# MicroControlador.net
KiCad netlist of a schematic drawn in Altium Designer
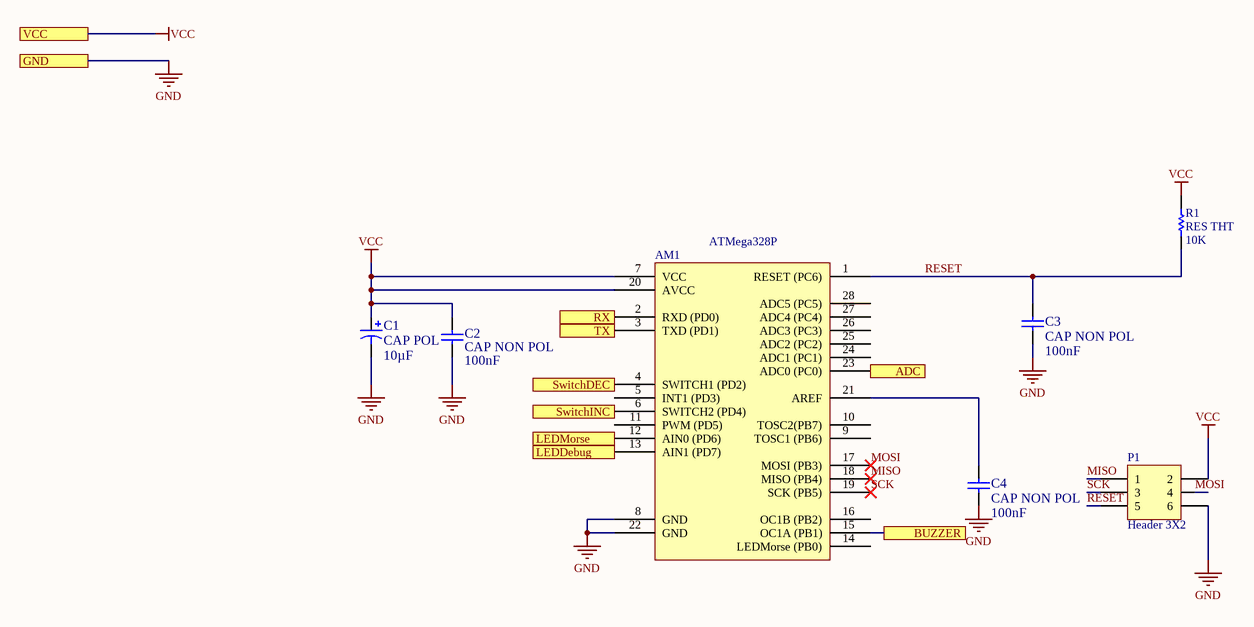
[diagram p0: MicroControlador.SchDoc]

(export (version "E")
  (design (tool "Eeschema 10.0.6"))
  (components
    (comp (ref "AM1")
      (value "ATMega328P")
      (footprint "ATMega328P")
      (libsource (lib "ATMega328P") (part "ATMega328P"))
    )
    (comp (ref "C1")
      (value "CAP POL")
      (footprint "CONDENS 10uF")
      (description "Polarized Capacitor (Axial)")
      (fields (field (name "ALTIUM_VALUE") "10µF") (field (name "PUBLISHER") "Altium Limited"))
      (libsource (lib "MySchem") (part "Cap Pol2"))
    )
    (comp (ref "C2")
      (value "CAP NON POL")
      (footprint "Capacitor 100nF")
      (description "Capacitor")
      (fields (field (name "ALTIUM_VALUE") "100nF") (field (name "PUBLISHER") "Altium Limited"))
      (libsource (lib "MySchem") (part "Cap"))
    )
    (comp (ref "C3")
      (value "CAP NON POL")
      (footprint "Capacitor 100nF")
      (description "Capacitor")
      (fields (field (name "ALTIUM_VALUE") "100nF") (field (name "PUBLISHER") "Altium Limited"))
      (libsource (lib "MySchem") (part "Cap"))
    )
    (comp (ref "C4")
      (value "CAP NON POL")
      (footprint "Capacitor 100nF")
      (description "Capacitor")
      (fields (field (name "ALTIUM_VALUE") "100nF") (field (name "PUBLISHER") "Altium Limited"))
      (libsource (lib "MySchem") (part "Cap"))
    )
    (comp (ref "P1")
      (value "Header 3X2")
      (footprint "Connector Header 3x2")
      (description "Header, 3-Pin, Dual row")
      (fields (field (name "PUBLISHER") "Altium Limited"))
      (libsource (lib "MySchematicConnector") (part "Header 3X2"))
    )
    (comp (ref "R1")
      (value "RES THT")
      (footprint "RESISTENCIA")
      (description "Resistor")
      (fields (field (name "ALTIUM_VALUE") "10K") (field (name "PUBLISHER") "Altium Limited"))
      (libsource (lib "MySchem") (part "Res1"))
    )
  )
  (nets
    (net (code "1") (name "/ADC") (class "Default")
      (node (ref "AM1") (pin "23") (pinfunction "ADC0_(PC0)_23") (pintype "passive"))
    )
    (net (code "2") (name "/BUZZER") (class "Default")
      (node (ref "AM1") (pin "15") (pinfunction "OC1A_(PB1)_15") (pintype "passive"))
    )
    (net (code "3") (name "/LEDDebug") (class "Default")
      (node (ref "AM1") (pin "13") (pinfunction "AIN1_(PD7)_13") (pintype "passive"))
    )
    (net (code "4") (name "/LEDMorse") (class "Default")
      (node (ref "AM1") (pin "12") (pinfunction "AIN0_(PD6)_12") (pintype "passive"))
    )
    (net (code "5") (name "/MISO") (class "Default")
      (node (ref "AM1") (pin "18") (pinfunction "MISO_(PB4)_18") (pintype "passive"))
      (node (ref "P1") (pin "1") (pinfunction "1_1") (pintype "passive"))
    )
    (net (code "6") (name "/MOSI") (class "Default")
      (node (ref "AM1") (pin "17") (pinfunction "MOSI_(PB3)_17") (pintype "passive"))
      (node (ref "P1") (pin "4") (pinfunction "4_4") (pintype "passive"))
    )
    (net (code "7") (name "/RESET") (class "Default")
      (node (ref "AM1") (pin "1") (pinfunction "RESET_(PC6)_1") (pintype "passive"))
      (node (ref "C3") (pin "2") (pinfunction "2_2") (pintype "passive"))
      (node (ref "P1") (pin "5") (pinfunction "5_5") (pintype "passive"))
      (node (ref "R1") (pin "1") (pinfunction "1_1") (pintype "passive"))
    )
    (net (code "8") (name "/RX") (class "Default")
      (node (ref "AM1") (pin "2") (pinfunction "RXD_(PD0)_2") (pintype "passive"))
    )
    (net (code "9") (name "/SCK") (class "Default")
      (node (ref "AM1") (pin "19") (pinfunction "SCK_(PB5)_19") (pintype "passive"))
      (node (ref "P1") (pin "3") (pinfunction "3_3") (pintype "passive"))
    )
    (net (code "10") (name "/SwitchDEC") (class "Default")
      (node (ref "AM1") (pin "4") (pinfunction "SWITCH1_(PD2)_4") (pintype "passive"))
    )
    (net (code "11") (name "/SwitchINC") (class "Default")
      (node (ref "AM1") (pin "6") (pinfunction "SWITCH2_(PD4)_6") (pintype "passive"))
    )
    (net (code "12") (name "/TX") (class "Default")
      (node (ref "AM1") (pin "3") (pinfunction "TXD_(PD1)_3") (pintype "passive"))
    )
    (net (code "13") (name "GND") (class "Default")
      (node (ref "AM1") (pin "22") (pinfunction "GND_22") (pintype "passive"))
      (node (ref "AM1") (pin "8") (pinfunction "GND_8") (pintype "passive"))
      (node (ref "C1") (pin "2") (pinfunction "2_2") (pintype "passive"))
      (node (ref "C2") (pin "2") (pinfunction "2_2") (pintype "passive"))
      (node (ref "C3") (pin "1") (pinfunction "1_1") (pintype "passive"))
      (node (ref "C4") (pin "1") (pinfunction "1_1") (pintype "passive"))
      (node (ref "P1") (pin "6") (pinfunction "6_6") (pintype "passive"))
    )
    (net (code "14") (name "Net-(AM1-AREF)") (class "Default")
      (node (ref "AM1") (pin "21") (pinfunction "AREF_21") (pintype "passive"))
      (node (ref "C4") (pin "2") (pinfunction "2_2") (pintype "passive"))
    )
    (net (code "15") (name "VCC") (class "Default")
      (node (ref "AM1") (pin "20") (pinfunction "AVCC_20") (pintype "passive"))
      (node (ref "AM1") (pin "7") (pinfunction "VCC_7") (pintype "passive"))
      (node (ref "C1") (pin "1") (pinfunction "1_1") (pintype "passive"))
      (node (ref "C2") (pin "1") (pinfunction "1_1") (pintype "passive"))
      (node (ref "P1") (pin "2") (pinfunction "2_2") (pintype "passive"))
      (node (ref "R1") (pin "2") (pinfunction "2_2") (pintype "passive"))
    )
    (net (code "16") (name "unconnected-(AM1-ADC1_(PC1)-Pad24)") (class "Default")
      (node (ref "AM1") (pin "24") (pinfunction "ADC1_(PC1)_24") (pintype "passive"))
    )
    (net (code "17") (name "unconnected-(AM1-ADC2_(PC2)-Pad25)") (class "Default")
      (node (ref "AM1") (pin "25") (pinfunction "ADC2_(PC2)_25") (pintype "passive"))
    )
    (net (code "18") (name "unconnected-(AM1-ADC3_(PC3)-Pad26)") (class "Default")
      (node (ref "AM1") (pin "26") (pinfunction "ADC3_(PC3)_26") (pintype "passive"))
    )
    (net (code "19") (name "unconnected-(AM1-ADC4_(PC4)-Pad27)") (class "Default")
      (node (ref "AM1") (pin "27") (pinfunction "ADC4_(PC4)_27") (pintype "passive"))
    )
    (net (code "20") (name "unconnected-(AM1-ADC5_(PC5)-Pad28)") (class "Default")
      (node (ref "AM1") (pin "28") (pinfunction "ADC5_(PC5)_28") (pintype "passive"))
    )
    (net (code "21") (name "unconnected-(AM1-INT1_(PD3)-Pad5)") (class "Default")
      (node (ref "AM1") (pin "5") (pinfunction "INT1_(PD3)_5") (pintype "passive"))
    )
    (net (code "22") (name "unconnected-(AM1-LEDMorse_(PB0)-Pad14)") (class "Default")
      (node (ref "AM1") (pin "14") (pinfunction "LEDMorse_(PB0)_14") (pintype "passive"))
    )
    (net (code "23") (name "unconnected-(AM1-OC1B_(PB2)-Pad16)") (class "Default")
      (node (ref "AM1") (pin "16") (pinfunction "OC1B_(PB2)_16") (pintype "passive"))
    )
    (net (code "24") (name "unconnected-(AM1-PWM_(PD5)-Pad11)") (class "Default")
      (node (ref "AM1") (pin "11") (pinfunction "PWM_(PD5)_11") (pintype "passive"))
    )
    (net (code "25") (name "unconnected-(AM1-TOSC1_(PB6)-Pad9)") (class "Default")
      (node (ref "AM1") (pin "9") (pinfunction "TOSC1_(PB6)_9") (pintype "passive"))
    )
    (net (code "26") (name "unconnected-(AM1-TOSC2(PB7)-Pad10)") (class "Default")
      (node (ref "AM1") (pin "10") (pinfunction "TOSC2(PB7)_10") (pintype "passive"))
    )
  )
)
